# 103_Button_Rev020000.net
KiCad netlist of a schematic drawn in EAGLE
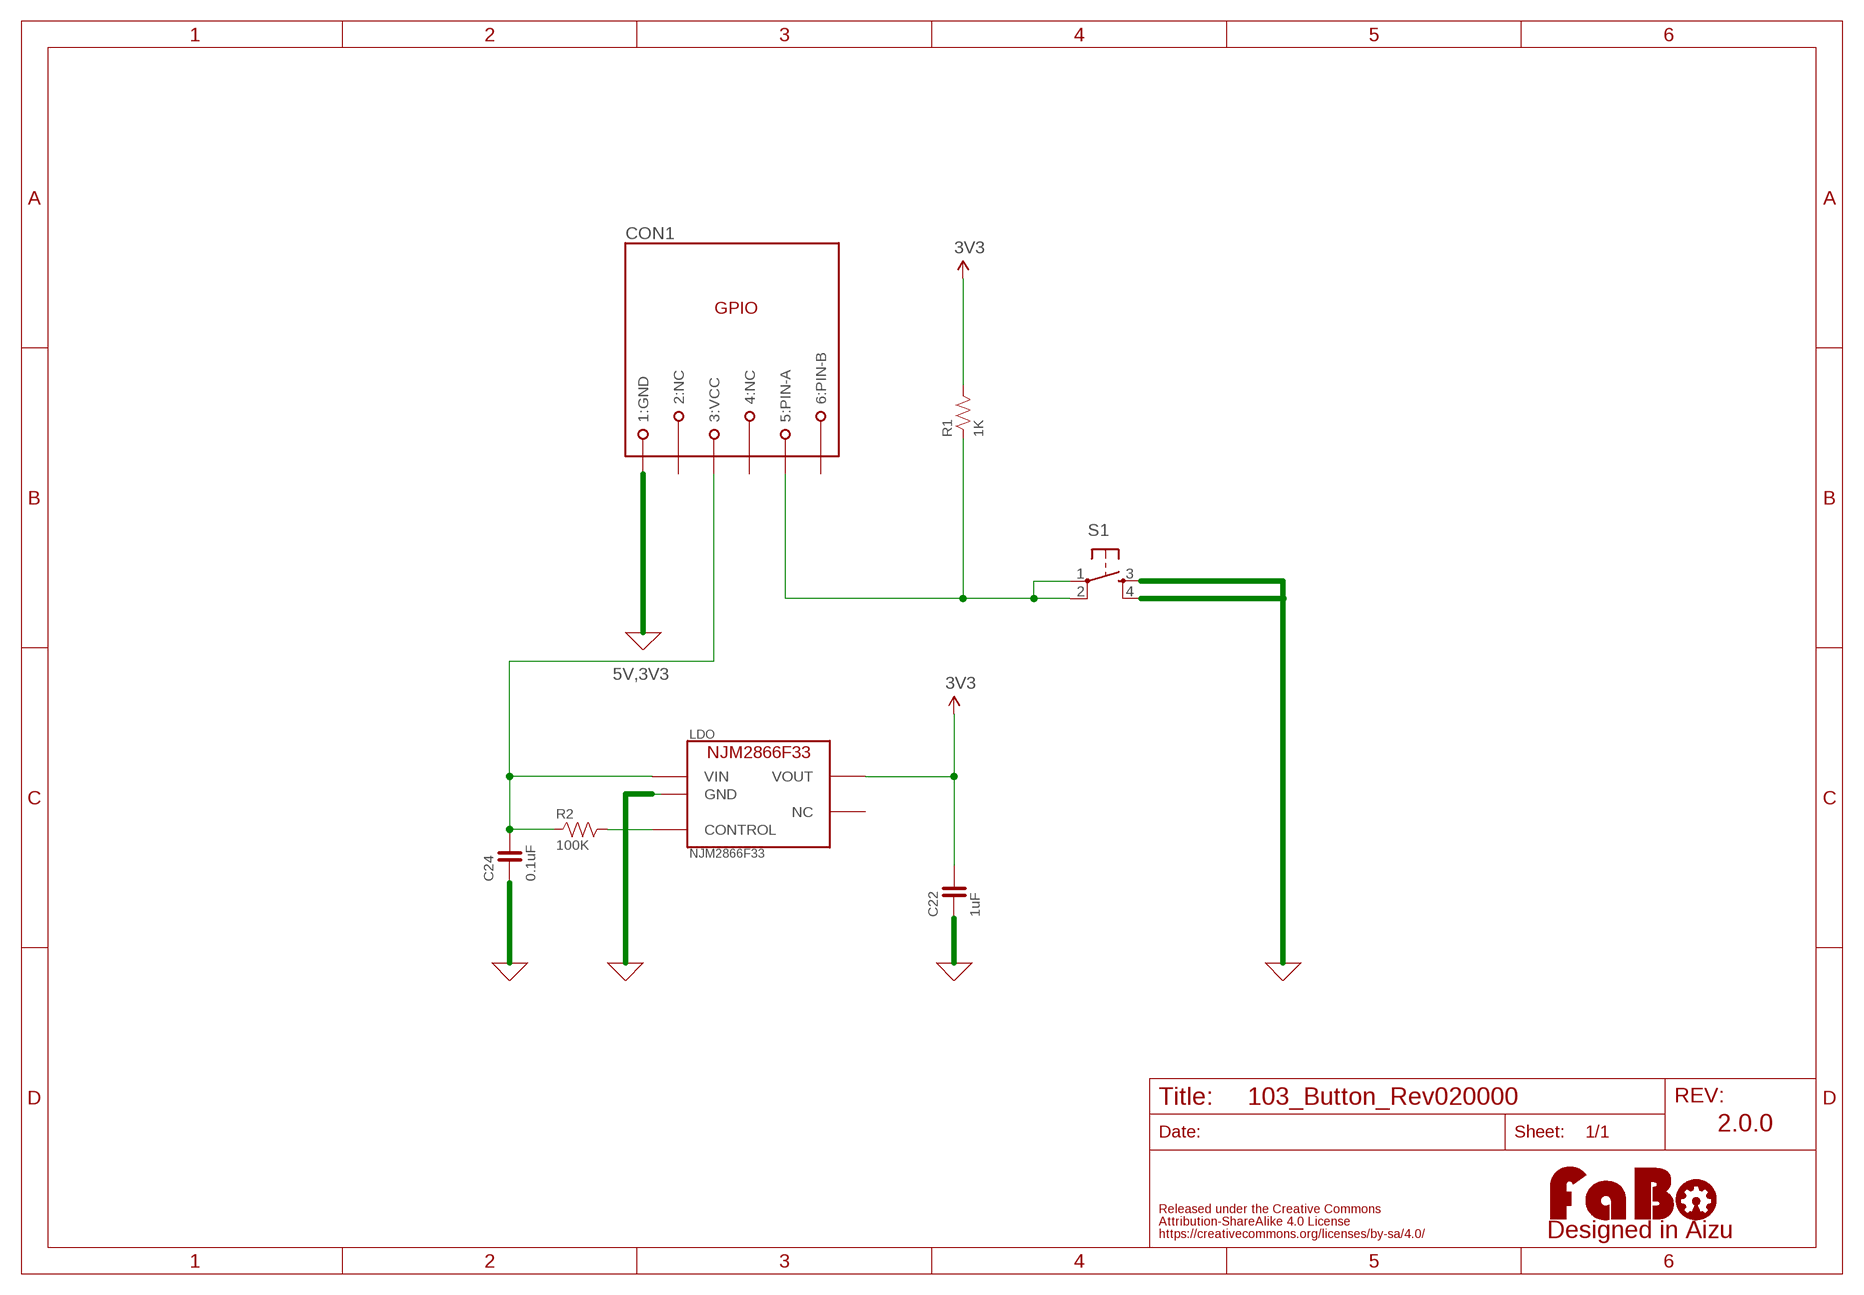
[diagram p0: schematic, sheet 1]

(export (version "E")
  (design (tool "Eeschema 10.0.6"))
  (components
    (comp (ref "C22")
      (value "1uF")
      (footprint "eagle-import:0603")
      (libsource (lib "eagle-import") (part "CAPACITOR-0603"))
    )
    (comp (ref "C24")
      (value "0.1uF")
      (footprint "eagle-import:0603")
      (libsource (lib "eagle-import") (part "CAPACITOR-0603"))
    )
    (comp (ref "CON1")
      (value "MODULAR-JACK-6P-RJ11_GPIO")
      (footprint "eagle-import:7002-6PXC-X")
      (libsource (lib "eagle-import") (part "MODULAR-JACK-6P-RJ11_GPIO"))
    )
    (comp (ref "LDO")
      (value "NJM2866F33")
      (footprint "eagle-import:SOT-23-5")
      (libsource (lib "eagle-import") (part "NJM2866F33"))
    )
    (comp (ref "LOGO1")
      (value "LOGO_FABO-M_BOTTOM")
      (footprint "eagle-import:LOGO_FABO_M_BOTTOM")
      (libsource (lib "eagle-import") (part "LOGO_FABO-M_BOTTOM"))
    )
    (comp (ref "R1")
      (value "1K")
      (footprint "eagle-import:0603")
      (libsource (lib "eagle-import") (part "RESISTOR-0603"))
    )
    (comp (ref "R2")
      (value "100K")
      (footprint "eagle-import:0603")
      (libsource (lib "eagle-import") (part "RESISTOR-0603"))
    )
    (comp (ref "S1")
      (value "TACT-SWITCH-12MM")
      (footprint "eagle-import:1273HA-160G-G")
      (libsource (lib "eagle-import") (part "TACT-SWITCH-12MM"))
    )
  )
  (nets
    (net (code "1") (name "/5V,3V3") (class "Default")
      (node (ref "C24") (pin "2") (pinfunction "2_2") (pintype "passive"))
      (node (ref "CON1") (pin "3") (pinfunction "3:VCC_3") (pintype "power_in"))
      (node (ref "LDO") (pin "1") (pinfunction "VIN_1") (pintype "input"))
      (node (ref "R2") (pin "1") (pinfunction "1_1") (pintype "bidirectional"))
    )
    (net (code "2") (name "3V3") (class "Default")
      (node (ref "C22") (pin "2") (pinfunction "2_2") (pintype "passive"))
      (node (ref "LDO") (pin "5") (pinfunction "VOUT_5") (pintype "output"))
      (node (ref "R1") (pin "2") (pinfunction "2_2") (pintype "bidirectional"))
    )
    (net (code "3") (name "GND") (class "Default")
      (node (ref "C22") (pin "1") (pinfunction "1_1") (pintype "passive"))
      (node (ref "C24") (pin "1") (pinfunction "1_1") (pintype "passive"))
      (node (ref "CON1") (pin "1") (pinfunction "1:GND_1") (pintype "power_in"))
      (node (ref "LDO") (pin "2") (pinfunction "GND_2") (pintype "power_in"))
      (node (ref "S1") (pin "3") (pinfunction "3_3") (pintype "passive"))
      (node (ref "S1") (pin "4") (pinfunction "4_4") (pintype "passive"))
    )
    (net (code "4") (name "Net-(CON1-5:PIN-A)") (class "Default")
      (node (ref "CON1") (pin "5") (pinfunction "5:PIN-A_5") (pintype "bidirectional"))
      (node (ref "R1") (pin "1") (pinfunction "1_1") (pintype "bidirectional"))
      (node (ref "S1") (pin "1") (pinfunction "1_1") (pintype "passive"))
      (node (ref "S1") (pin "2") (pinfunction "2_2") (pintype "passive"))
    )
    (net (code "5") (name "Net-(LDO-CONTROL)") (class "Default")
      (node (ref "LDO") (pin "3") (pinfunction "CONTROL_3") (pintype "input"))
      (node (ref "R2") (pin "2") (pinfunction "2_2") (pintype "bidirectional"))
    )
    (net (code "6") (name "unconnected-(CON1-2:NC-Pad2)") (class "Default")
      (node (ref "CON1") (pin "2") (pinfunction "2:NC_2") (pintype "no_connect"))
    )
    (net (code "7") (name "unconnected-(CON1-4:NC-Pad4)") (class "Default")
      (node (ref "CON1") (pin "4") (pinfunction "4:NC_4") (pintype "no_connect"))
    )
    (net (code "8") (name "unconnected-(CON1-6:PIN-B-Pad6)") (class "Default")
      (node (ref "CON1") (pin "6") (pinfunction "6:PIN-B_6") (pintype "bidirectional"))
    )
    (net (code "9") (name "unconnected-(LDO-NC-Pad4)") (class "Default")
      (node (ref "LDO") (pin "4") (pinfunction "NC_4") (pintype "no_connect"))
    )
  )
)
